# MCU.net
KiCad netlist of a schematic drawn in Altium Designer
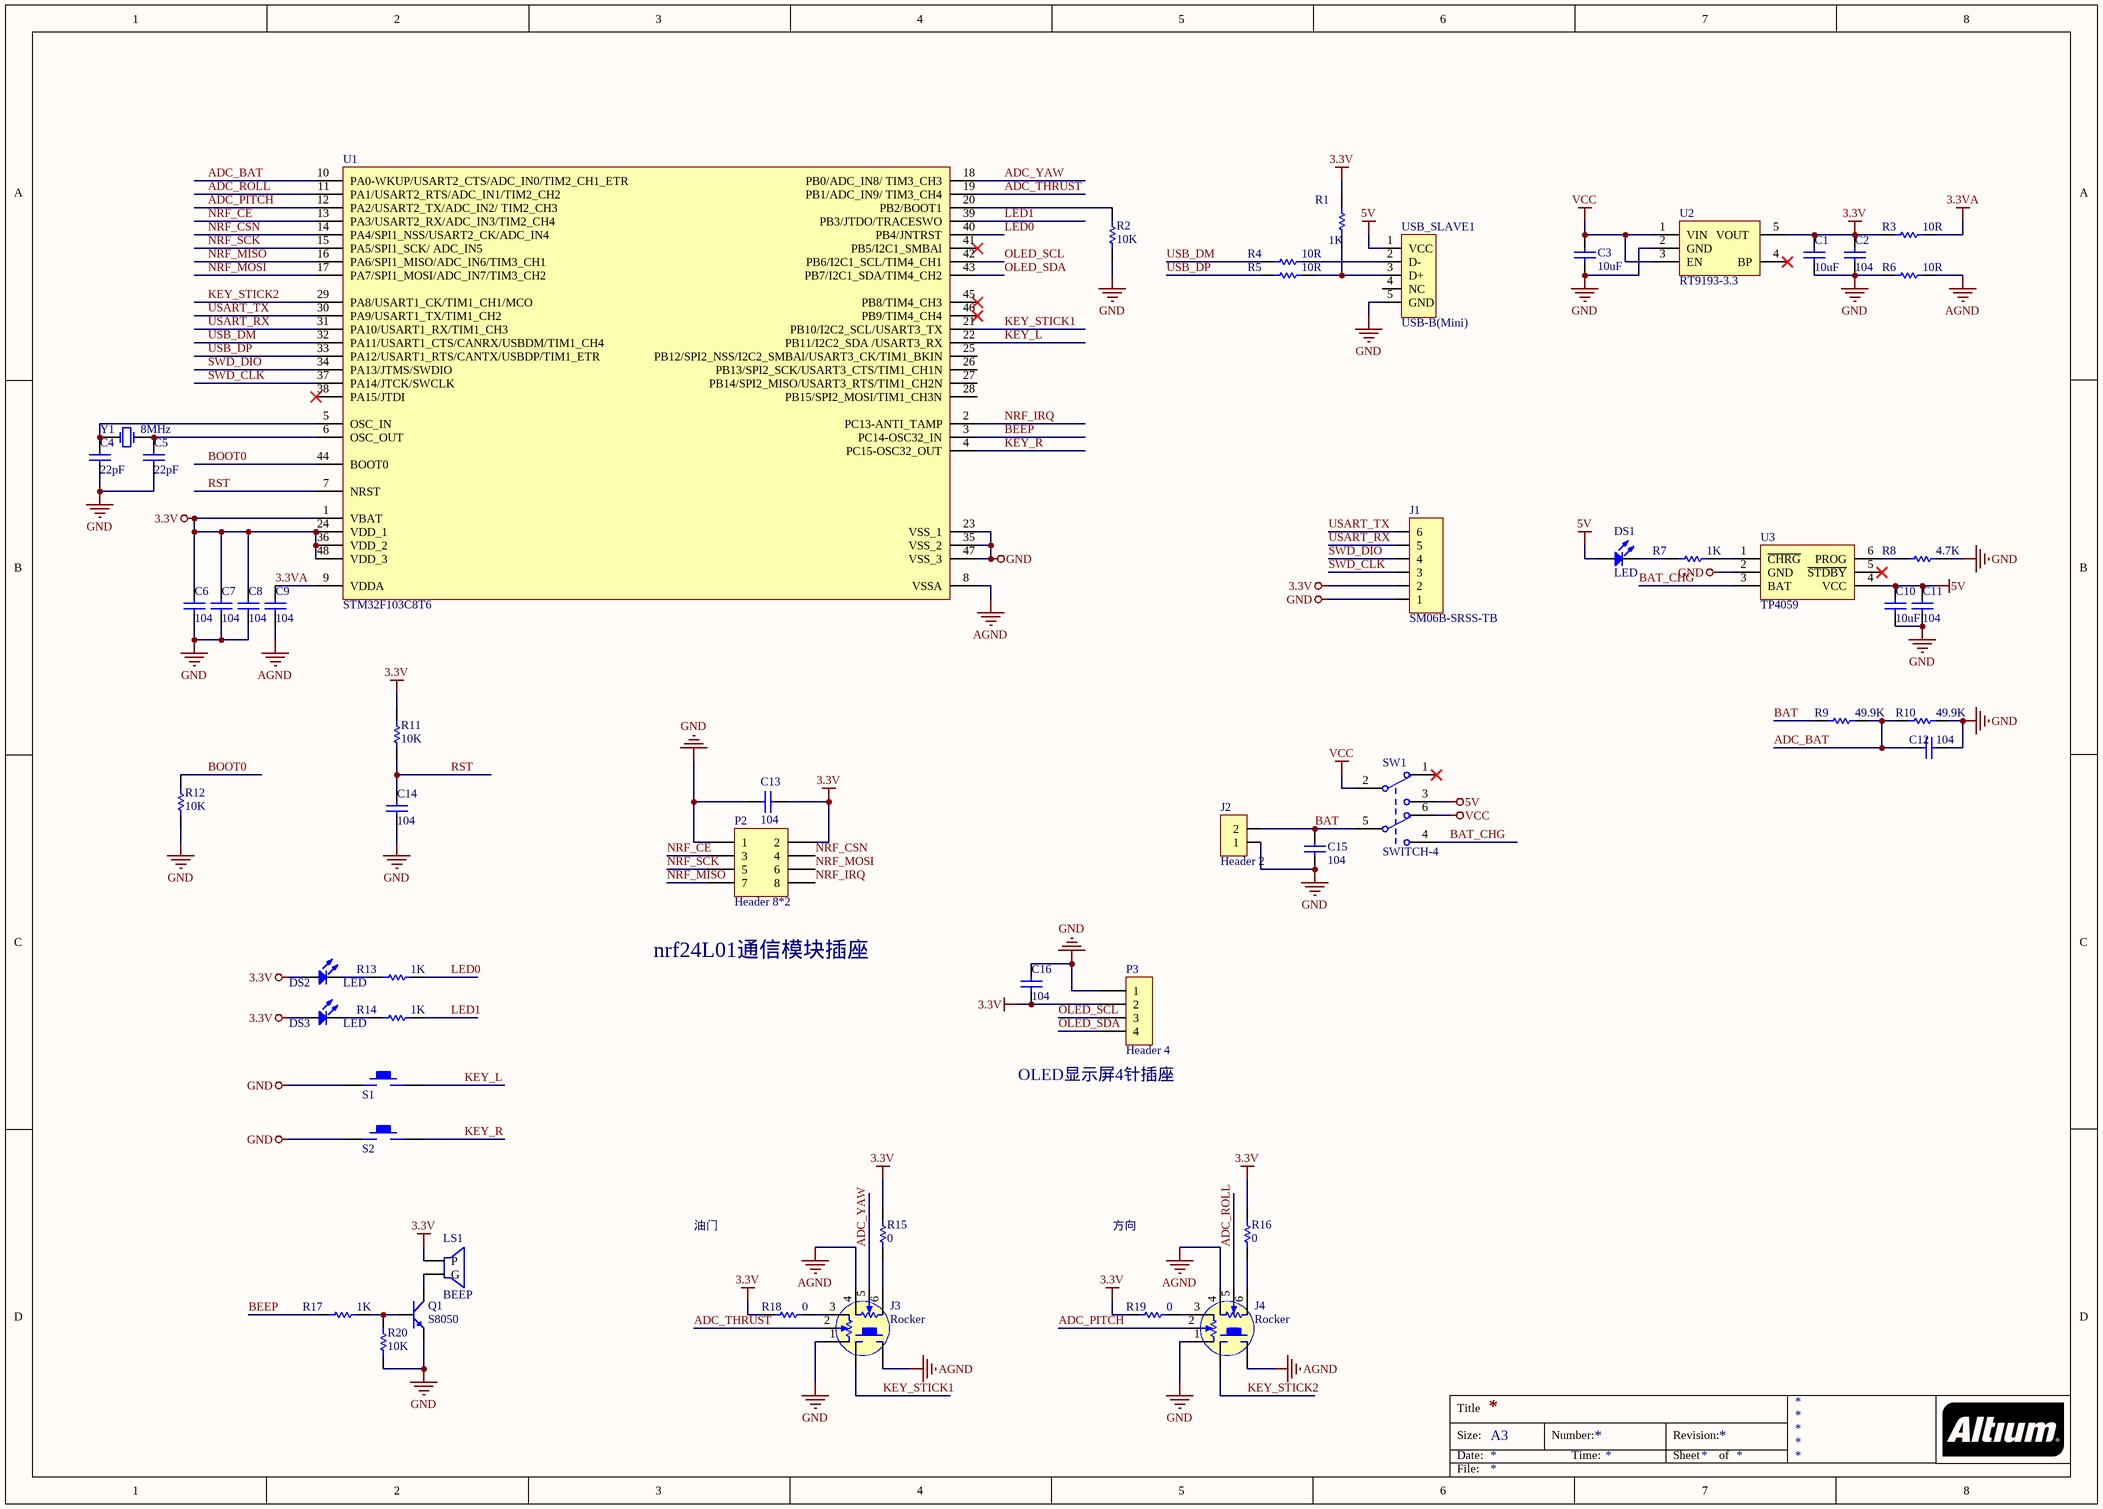
[diagram p0: MCU.SchDoc]

(export (version "E")
  (design (tool "Eeschema 10.0.6"))
  (components
    (comp (ref "C1")
      (value "10uF")
      (footprint "C0603")
      (description "电容")
      (fields (field (name "PUBLISHER") "Altium Limited"))
      (libsource (lib "Devices") (part "C0603"))
    )
    (comp (ref "C2")
      (value "104")
      (footprint "C0603")
      (description "电容")
      (fields (field (name "PUBLISHER") "Altium Limited"))
      (libsource (lib "Devices") (part "C0603"))
    )
    (comp (ref "C3")
      (value "10uF")
      (footprint "C0603")
      (description "电容")
      (fields (field (name "PUBLISHER") "Altium Limited"))
      (libsource (lib "Devices") (part "C0603"))
    )
    (comp (ref "C4")
      (value "22pF")
      (footprint "C0603")
      (description "电容")
      (fields (field (name "PUBLISHER") "Altium Limited"))
      (libsource (lib "Devices") (part "C0603"))
    )
    (comp (ref "C5")
      (value "22pF")
      (footprint "C0603")
      (description "电容")
      (fields (field (name "PUBLISHER") "Altium Limited"))
      (libsource (lib "Devices") (part "C0603"))
    )
    (comp (ref "C6")
      (value "104")
      (footprint "C0603")
      (description "电容")
      (fields (field (name "PUBLISHER") "Altium Limited"))
      (libsource (lib "Devices") (part "C0603"))
    )
    (comp (ref "C7")
      (value "104")
      (footprint "C0603")
      (description "电容")
      (fields (field (name "PUBLISHER") "Altium Limited"))
      (libsource (lib "Devices") (part "C0603"))
    )
    (comp (ref "C8")
      (value "104")
      (footprint "C0603")
      (description "电容")
      (fields (field (name "PUBLISHER") "Altium Limited"))
      (libsource (lib "Devices") (part "C0603"))
    )
    (comp (ref "C9")
      (value "104")
      (footprint "C0603")
      (description "电容")
      (fields (field (name "PUBLISHER") "Altium Limited"))
      (libsource (lib "Devices") (part "C0603"))
    )
    (comp (ref "C10")
      (value "10uF")
      (footprint "C0603")
      (description "电容")
      (fields (field (name "PUBLISHER") "Altium Limited"))
      (libsource (lib "Devices") (part "C0603"))
    )
    (comp (ref "C11")
      (value "104")
      (footprint "C0603")
      (description "电容")
      (fields (field (name "PUBLISHER") "Altium Limited"))
      (libsource (lib "Devices") (part "C0603"))
    )
    (comp (ref "C12")
      (value "104")
      (footprint "C0603")
      (description "电容")
      (fields (field (name "PUBLISHER") "Altium Limited"))
      (libsource (lib "Devices") (part "C0603"))
    )
    (comp (ref "C13")
      (value "104")
      (footprint "C0603")
      (description "电容")
      (fields (field (name "PUBLISHER") "Altium Limited"))
      (libsource (lib "Devices") (part "C0603"))
    )
    (comp (ref "C14")
      (value "104")
      (footprint "C0603")
      (description "电容")
      (fields (field (name "PUBLISHER") "Altium Limited"))
      (libsource (lib "Devices") (part "C0603"))
    )
    (comp (ref "C15")
      (value "104")
      (footprint "C0603")
      (description "电容")
      (fields (field (name "PUBLISHER") "Altium Limited"))
      (libsource (lib "Devices") (part "C0603"))
    )
    (comp (ref "C16")
      (value "104")
      (footprint "C0603")
      (description "电容")
      (fields (field (name "PUBLISHER") "Altium Limited"))
      (libsource (lib "Devices") (part "C0603"))
    )
    (comp (ref "DS1")
      (value "LED")
      (footprint "LED0603")
      (description "Typical RED, GREEN, YELLOW, AMBER GaAs LED")
      (fields (field (name "PUBLISHER") "Altium Limited"))
      (libsource (lib "Devices") (part "LED"))
    )
    (comp (ref "DS2")
      (value "LED")
      (footprint "LED0603")
      (description "Typical RED, GREEN, YELLOW, AMBER GaAs LED")
      (fields (field (name "PUBLISHER") "Altium Limited"))
      (libsource (lib "Devices") (part "LED"))
    )
    (comp (ref "DS3")
      (value "LED")
      (footprint "LED0603")
      (description "Typical RED, GREEN, YELLOW, AMBER GaAs LED")
      (fields (field (name "PUBLISHER") "Altium Limited"))
      (libsource (lib "Devices") (part "LED"))
    )
    (comp (ref "J1")
      (value "SM06B-SRSS-TB")
      (footprint "HDR1X6")
      (libsource (lib "Connectors") (part "SM06B-SRSS-TB"))
    )
    (comp (ref "J2")
      (value "Header 2")
      (footprint "HDR1X2-2MM")
      (description "Header, 2-Pin")
      (fields (field (name "PUBLISHER") "Altium Limited"))
      (libsource (lib "Connectors") (part "Header 2"))
    )
    (comp (ref "J3")
      (value "Rocker")
      (footprint "Rocker-RKJXV1224005")
      (description "航模摇杆")
      (libsource (lib "Devices") (part "Rocker"))
    )
    (comp (ref "J4")
      (value "Rocker")
      (footprint "Rocker-RKJXV1224005")
      (description "航模摇杆")
      (libsource (lib "Devices") (part "Rocker"))
    )
    (comp (ref "LS1")
      (value "BEEP")
      (footprint "BEEP-9")
      (description "蜂鸣器")
      (libsource (lib "Devices") (part "BEEP"))
    )
    (comp (ref "P2")
      (value "Header 8*2")
      (footprint "HDR4*2")
      (description "Header, 8-Pin")
      (fields (field (name "PUBLISHER") "Altium Limited"))
      (libsource (lib "Remoter") (part "Header 4*2"))
    )
    (comp (ref "P3")
      (value "Header 4")
      (footprint "HDR1X4")
      (description "Header, 8-Pin")
      (fields (field (name "PUBLISHER") "Altium Limited"))
      (libsource (lib "Remoter") (part "Header 4"))
    )
    (comp (ref "Q1")
      (value "S8050")
      (footprint "SOT-23R")
      (description "8050/BCW846/BCW847")
      (libsource (lib "Devices") (part "NPN"))
    )
    (comp (ref "R1")
      (value "1K")
      (footprint "R0603")
      (description "电阻")
      (fields (field (name "PUBLISHER") "Altium Limited"))
      (libsource (lib "Devices") (part "RES0603"))
    )
    (comp (ref "R2")
      (value "10K")
      (footprint "R0603")
      (description "电阻")
      (fields (field (name "PUBLISHER") "Altium Limited"))
      (libsource (lib "Devices") (part "RES0603"))
    )
    (comp (ref "R3")
      (value "10R")
      (footprint "R0603")
      (description "电阻")
      (fields (field (name "PUBLISHER") "Altium Limited"))
      (libsource (lib "Devices") (part "RES0603"))
    )
    (comp (ref "R4")
      (value "10R")
      (footprint "R0603")
      (description "电阻")
      (fields (field (name "PUBLISHER") "Altium Limited"))
      (libsource (lib "Devices") (part "RES0603"))
    )
    (comp (ref "R5")
      (value "10R")
      (footprint "R0603")
      (description "电阻")
      (fields (field (name "PUBLISHER") "Altium Limited"))
      (libsource (lib "Devices") (part "RES0603"))
    )
    (comp (ref "R6")
      (value "10R")
      (footprint "R0603")
      (description "电阻")
      (fields (field (name "PUBLISHER") "Altium Limited"))
      (libsource (lib "Devices") (part "RES0603"))
    )
    (comp (ref "R7")
      (value "1K")
      (footprint "R0603")
      (description "电阻")
      (fields (field (name "PUBLISHER") "Altium Limited"))
      (libsource (lib "Devices") (part "RES0603"))
    )
    (comp (ref "R8")
      (value "4.7K")
      (footprint "R0603")
      (description "电阻")
      (fields (field (name "PUBLISHER") "Altium Limited"))
      (libsource (lib "Devices") (part "RES0603"))
    )
    (comp (ref "R9")
      (value "49.9K")
      (footprint "R0603")
      (description "电阻")
      (fields (field (name "PUBLISHER") "Altium Limited"))
      (libsource (lib "Devices") (part "RES0603"))
    )
    (comp (ref "R10")
      (value "49.9K")
      (footprint "R0603")
      (description "电阻")
      (fields (field (name "PUBLISHER") "Altium Limited"))
      (libsource (lib "Devices") (part "RES0603"))
    )
    (comp (ref "R11")
      (value "10K")
      (footprint "R0603")
      (description "电阻")
      (fields (field (name "PUBLISHER") "Altium Limited"))
      (libsource (lib "Devices") (part "RES0603"))
    )
    (comp (ref "R12")
      (value "10K")
      (footprint "R0603")
      (description "电阻")
      (fields (field (name "PUBLISHER") "Altium Limited"))
      (libsource (lib "Devices") (part "RES0603"))
    )
    (comp (ref "R13")
      (value "1K")
      (footprint "R0603")
      (description "电阻")
      (fields (field (name "PUBLISHER") "Altium Limited"))
      (libsource (lib "Devices") (part "RES0603"))
    )
    (comp (ref "R14")
      (value "1K")
      (footprint "R0603")
      (description "电阻")
      (fields (field (name "PUBLISHER") "Altium Limited"))
      (libsource (lib "Devices") (part "RES0603"))
    )
    (comp (ref "R15")
      (value "0")
      (footprint "R0603")
      (description "电阻")
      (fields (field (name "PUBLISHER") "Altium Limited"))
      (libsource (lib "Devices") (part "RES0603"))
    )
    (comp (ref "R16")
      (value "0")
      (footprint "R0603")
      (description "电阻")
      (fields (field (name "PUBLISHER") "Altium Limited"))
      (libsource (lib "Devices") (part "RES0603"))
    )
    (comp (ref "R17")
      (value "1K")
      (footprint "R0603")
      (description "电阻")
      (fields (field (name "PUBLISHER") "Altium Limited"))
      (libsource (lib "Devices") (part "RES0603"))
    )
    (comp (ref "R18")
      (value "0")
      (footprint "R0603")
      (description "电阻")
      (fields (field (name "PUBLISHER") "Altium Limited"))
      (libsource (lib "Devices") (part "RES0603"))
    )
    (comp (ref "R19")
      (value "0")
      (footprint "R0603")
      (description "电阻")
      (fields (field (name "PUBLISHER") "Altium Limited"))
      (libsource (lib "Devices") (part "RES0603"))
    )
    (comp (ref "R20")
      (value "10K")
      (footprint "R0603")
      (description "电阻")
      (fields (field (name "PUBLISHER") "Altium Limited"))
      (libsource (lib "Devices") (part "RES0603"))
    )
    (comp (ref "S1")
      (value "KEY")
      (footprint "KEY-3X6X3.5-C")
      (description "普通轻触按钮")
      (libsource (lib "Devices") (part "KEY"))
    )
    (comp (ref "S2")
      (value "KEY")
      (footprint "KEY-3X6X3.5-C")
      (description "普通轻触按钮")
      (libsource (lib "Devices") (part "KEY"))
    )
    (comp (ref "SW1")
      (value "SWITCH-4")
      (footprint "SW-MSS22D18G2")
      (libsource (lib "Devices") (part "SWITCH-4"))
    )
    (comp (ref "U1")
      (value "STM32F103C8T6")
      (footprint "LQFP-48")
      (libsource (lib "IC") (part "STM32F103C8T6"))
    )
    (comp (ref "U2") (value "RT9193-3.3") (footprint "SOT-23-5") (libsource (lib "IC") (part "RT9193-3.3")))
    (comp (ref "U3")
      (value "TP4059")
      (footprint "SOT23-6")
      (description "锂电池充电IC")
      (libsource (lib "IC") (part "TP4059"))
    )
    (comp (ref "USB_SLAVE1")
      (value "USB-B(Mini)")
      (footprint "USB-MicroUSB")
      (libsource (lib "Connectors") (part "USB5"))
    )
    (comp (ref "Y1")
      (value "8MHz")
      (footprint "X-NX5032GA")
      (description "Crystal Oscillator")
      (fields (field (name "PUBLISHER") "Altium Limited"))
      (libsource (lib "Devices") (part "XTAL"))
    )
  )
  (nets
    (net (code "1") (name "/ADC_BAT") (class "Default")
      (node (ref "C12") (pin "2") (pinfunction "2_2") (pintype "passive"))
      (node (ref "R10") (pin "1") (pinfunction "1_1") (pintype "passive"))
      (node (ref "R9") (pin "2") (pinfunction "2_2") (pintype "passive"))
      (node (ref "U1") (pin "10") (pinfunction "PA0-WKUP/USART2_CTS/ADC_IN0/TIM2_CH1_ETR_10") (pintype "passive"))
    )
    (net (code "2") (name "/ADC_PITCH") (class "Default")
      (node (ref "J4") (pin "2") (pinfunction "2_2") (pintype "passive"))
      (node (ref "U1") (pin "12") (pinfunction "PA2/USART2_TX/ADC_IN2/_TIM2_CH3_12") (pintype "passive"))
    )
    (net (code "3") (name "/ADC_ROLL") (class "Default")
      (node (ref "J4") (pin "5") (pinfunction "5_5") (pintype "passive"))
      (node (ref "U1") (pin "11") (pinfunction "PA1/USART2_RTS/ADC_IN1/TIM2_CH2_11") (pintype "passive"))
    )
    (net (code "4") (name "/ADC_THRUST") (class "Default")
      (node (ref "J3") (pin "2") (pinfunction "2_2") (pintype "passive"))
      (node (ref "U1") (pin "19") (pinfunction "PB1/ADC_IN9/_TIM3_CH4_19") (pintype "passive"))
    )
    (net (code "5") (name "/ADC_YAW") (class "Default")
      (node (ref "J3") (pin "5") (pinfunction "5_5") (pintype "passive"))
      (node (ref "U1") (pin "18") (pinfunction "PB0/ADC_IN8/_TIM3_CH3_18") (pintype "passive"))
    )
    (net (code "6") (name "/BAT") (class "Default")
      (node (ref "C15") (pin "1") (pinfunction "1_1") (pintype "passive"))
      (node (ref "J2") (pin "2") (pinfunction "2_2") (pintype "passive"))
      (node (ref "R9") (pin "1") (pinfunction "1_1") (pintype "passive"))
      (node (ref "SW1") (pin "5") (pinfunction "5_5") (pintype "passive"))
    )
    (net (code "7") (name "/BAT_CHG") (class "Default")
      (node (ref "SW1") (pin "4") (pinfunction "4_4") (pintype "passive"))
      (node (ref "U3") (pin "3") (pinfunction "BAT_3") (pintype "passive"))
    )
    (net (code "8") (name "/BEEP") (class "Default")
      (node (ref "R17") (pin "1") (pinfunction "1_1") (pintype "passive"))
      (node (ref "U1") (pin "3") (pinfunction "PC14-OSC32_IN_3") (pintype "passive"))
    )
    (net (code "9") (name "/BOOT0") (class "Default")
      (node (ref "R12") (pin "2") (pinfunction "2_2") (pintype "passive"))
      (node (ref "U1") (pin "44") (pinfunction "BOOT0_44") (pintype "passive"))
    )
    (net (code "10") (name "/KEY_L") (class "Default")
      (node (ref "S1") (pin "2") (pinfunction "2_2") (pintype "passive"))
      (node (ref "U1") (pin "22") (pinfunction "PB11/I2C2_SDA_/USART3_RX_22") (pintype "passive"))
    )
    (net (code "11") (name "/KEY_R") (class "Default")
      (node (ref "S2") (pin "2") (pinfunction "2_2") (pintype "passive"))
      (node (ref "U1") (pin "4") (pinfunction "PC15-OSC32_OUT_4") (pintype "passive"))
    )
    (net (code "12") (name "/KEY_STICK1") (class "Default")
      (node (ref "J3") (pin "J2") (pinfunction "J2_J2") (pintype "passive"))
      (node (ref "U1") (pin "21") (pinfunction "PB10/I2C2_SCL/USART3_TX_21") (pintype "passive"))
    )
    (net (code "13") (name "/KEY_STICK2") (class "Default")
      (node (ref "J4") (pin "J2") (pinfunction "J2_J2") (pintype "passive"))
      (node (ref "U1") (pin "29") (pinfunction "PA8/USART1_CK/TIM1_CH1/MCO_29") (pintype "passive"))
    )
    (net (code "14") (name "/LED0") (class "Default")
      (node (ref "R13") (pin "2") (pinfunction "2_2") (pintype "passive"))
      (node (ref "U1") (pin "40") (pinfunction "PB4/JNTRST_40") (pintype "passive"))
    )
    (net (code "15") (name "/LED1") (class "Default")
      (node (ref "R14") (pin "2") (pinfunction "2_2") (pintype "passive"))
      (node (ref "U1") (pin "39") (pinfunction "PB3/JTDO/TRACESWO_39") (pintype "passive"))
    )
    (net (code "16") (name "/NRF_CE") (class "Default")
      (node (ref "P2") (pin "3") (pinfunction "3_3") (pintype "passive"))
      (node (ref "U1") (pin "13") (pinfunction "PA3/USART2_RX/ADC_IN3/TIM2_CH4_13") (pintype "passive"))
    )
    (net (code "17") (name "/NRF_CSN") (class "Default")
      (node (ref "P2") (pin "4") (pinfunction "4_4") (pintype "passive"))
      (node (ref "U1") (pin "14") (pinfunction "PA4/SPI1_NSS/USART2_CK/ADC_IN4_14") (pintype "passive"))
    )
    (net (code "18") (name "/NRF_IRQ") (class "Default")
      (node (ref "P2") (pin "8") (pinfunction "8_8") (pintype "passive"))
      (node (ref "U1") (pin "2") (pinfunction "PC13-ANTI_TAMP_2") (pintype "passive"))
    )
    (net (code "19") (name "/NRF_MISO") (class "Default")
      (node (ref "P2") (pin "7") (pinfunction "7_7") (pintype "passive"))
      (node (ref "U1") (pin "16") (pinfunction "PA6/SPI1_MISO/ADC_IN6/TIM3_CH1_16") (pintype "passive"))
    )
    (net (code "20") (name "/NRF_MOSI") (class "Default")
      (node (ref "P2") (pin "6") (pinfunction "6_6") (pintype "passive"))
      (node (ref "U1") (pin "17") (pinfunction "PA7/SPI1_MOSI/ADC_IN7/TIM3_CH2_17") (pintype "passive"))
    )
    (net (code "21") (name "/NRF_SCK") (class "Default")
      (node (ref "P2") (pin "5") (pinfunction "5_5") (pintype "passive"))
      (node (ref "U1") (pin "15") (pinfunction "PA5/SPI1_SCK/_ADC_IN5_15") (pintype "passive"))
    )
    (net (code "22") (name "/OLED_SCL") (class "Default")
      (node (ref "P3") (pin "3") (pinfunction "3_3") (pintype "passive"))
      (node (ref "U1") (pin "42") (pinfunction "PB6/I2C1_SCL/TIM4_CH1_42") (pintype "passive"))
    )
    (net (code "23") (name "/OLED_SDA") (class "Default")
      (node (ref "P3") (pin "4") (pinfunction "4_4") (pintype "passive"))
      (node (ref "U1") (pin "43") (pinfunction "PB7/I2C1_SDA/TIM4_CH2_43") (pintype "passive"))
    )
    (net (code "24") (name "/RST") (class "Default")
      (node (ref "C14") (pin "2") (pinfunction "2_2") (pintype "passive"))
      (node (ref "R11") (pin "1") (pinfunction "1_1") (pintype "passive"))
      (node (ref "U1") (pin "7") (pinfunction "NRST_7") (pintype "passive"))
    )
    (net (code "25") (name "/SWD_CLK") (class "Default")
      (node (ref "J1") (pin "3") (pinfunction "3_3") (pintype "passive"))
      (node (ref "U1") (pin "37") (pinfunction "PA14/JTCK/SWCLK_37") (pintype "passive"))
    )
    (net (code "26") (name "/SWD_DIO") (class "Default")
      (node (ref "J1") (pin "4") (pinfunction "4_4") (pintype "passive"))
      (node (ref "U1") (pin "34") (pinfunction "PA13/JTMS/SWDIO_34") (pintype "passive"))
    )
    (net (code "27") (name "/USART_RX") (class "Default")
      (node (ref "J1") (pin "5") (pinfunction "5_5") (pintype "passive"))
      (node (ref "U1") (pin "31") (pinfunction "PA10/USART1_RX/TIM1_CH3_31") (pintype "passive"))
    )
    (net (code "28") (name "/USART_TX") (class "Default")
      (node (ref "J1") (pin "6") (pinfunction "6_6") (pintype "passive"))
      (node (ref "U1") (pin "30") (pinfunction "PA9/USART1_TX/TIM1_CH2_30") (pintype "passive"))
    )
    (net (code "29") (name "/USB_DM") (class "Default")
      (node (ref "R4") (pin "1") (pinfunction "1_1") (pintype "passive"))
      (node (ref "U1") (pin "32") (pinfunction "PA11/USART1_CTS/CANRX/USBDM/TIM1_CH4_32") (pintype "passive"))
    )
    (net (code "30") (name "/USB_DP") (class "Default")
      (node (ref "R5") (pin "1") (pinfunction "1_1") (pintype "passive"))
      (node (ref "U1") (pin "33") (pinfunction "PA12/USART1_RTS/CANTX/USBDP/TIM1_ETR_33") (pintype "passive"))
    )
    (net (code "31") (name "3.3V") (class "Default")
      (node (ref "C1") (pin "2") (pinfunction "2_2") (pintype "passive"))
      (node (ref "C13") (pin "2") (pinfunction "2_2") (pintype "passive"))
      (node (ref "C16") (pin "2") (pinfunction "2_2") (pintype "passive"))
      (node (ref "C2") (pin "2") (pinfunction "2_2") (pintype "passive"))
      (node (ref "C6") (pin "2") (pinfunction "2_2") (pintype "passive"))
      (node (ref "C7") (pin "2") (pinfunction "2_2") (pintype "passive"))
      (node (ref "C8") (pin "2") (pinfunction "2_2") (pintype "passive"))
      (node (ref "DS2") (pin "1") (pinfunction "A_1") (pintype "passive"))
      (node (ref "DS3") (pin "1") (pinfunction "A_1") (pintype "passive"))
      (node (ref "J1") (pin "2") (pinfunction "2_2") (pintype "passive"))
      (node (ref "LS1") (pin "1") (pinfunction "P_1") (pintype "passive"))
      (node (ref "P2") (pin "2") (pinfunction "2_2") (pintype "passive"))
      (node (ref "P3") (pin "2") (pinfunction "2_2") (pintype "passive"))
      (node (ref "R1") (pin "2") (pinfunction "2_2") (pintype "passive"))
      (node (ref "R11") (pin "2") (pinfunction "2_2") (pintype "passive"))
      (node (ref "R15") (pin "2") (pinfunction "2_2") (pintype "passive"))
      (node (ref "R16") (pin "2") (pinfunction "2_2") (pintype "passive"))
      (node (ref "R18") (pin "2") (pinfunction "2_2") (pintype "passive"))
      (node (ref "R19") (pin "2") (pinfunction "2_2") (pintype "passive"))
      (node (ref "R3") (pin "1") (pinfunction "1_1") (pintype "passive"))
      (node (ref "U1") (pin "1") (pinfunction "VBAT_1") (pintype "passive"))
      (node (ref "U1") (pin "24") (pinfunction "VDD_1_24") (pintype "passive"))
      (node (ref "U1") (pin "36") (pinfunction "VDD_2_36") (pintype "passive"))
      (node (ref "U1") (pin "48") (pinfunction "VDD_3_48") (pintype "passive"))
      (node (ref "U2") (pin "5") (pinfunction "VOUT_5") (pintype "passive"))
    )
    (net (code "32") (name "3.3VA") (class "Default")
      (node (ref "C9") (pin "2") (pinfunction "2_2") (pintype "passive"))
      (node (ref "R3") (pin "2") (pinfunction "2_2") (pintype "passive"))
      (node (ref "U1") (pin "9") (pinfunction "VDDA_9") (pintype "passive"))
    )
    (net (code "33") (name "5V") (class "Default")
      (node (ref "C10") (pin "2") (pinfunction "2_2") (pintype "passive"))
      (node (ref "C11") (pin "2") (pinfunction "2_2") (pintype "passive"))
      (node (ref "DS1") (pin "1") (pinfunction "A_1") (pintype "passive"))
      (node (ref "SW1") (pin "3") (pinfunction "3_3") (pintype "passive"))
      (node (ref "U3") (pin "4") (pinfunction "VCC_4") (pintype "passive"))
      (node (ref "USB_SLAVE1") (pin "1") (pinfunction "VCC_1") (pintype "passive"))
    )
    (net (code "34") (name "AGND") (class "Default")
      (node (ref "C9") (pin "1") (pinfunction "1_1") (pintype "passive"))
      (node (ref "J3") (pin "4") (pinfunction "4_4") (pintype "passive"))
      (node (ref "J3") (pin "J1") (pinfunction "J1_J1") (pintype "passive"))
      (node (ref "J4") (pin "4") (pinfunction "4_4") (pintype "passive"))
      (node (ref "J4") (pin "J1") (pinfunction "J1_J1") (pintype "passive"))
      (node (ref "R6") (pin "2") (pinfunction "2_2") (pintype "passive"))
      (node (ref "U1") (pin "8") (pinfunction "VSSA_8") (pintype "passive"))
    )
    (net (code "35") (name "GND") (class "Default")
      (node (ref "C1") (pin "1") (pinfunction "1_1") (pintype "passive"))
      (node (ref "C10") (pin "1") (pinfunction "1_1") (pintype "passive"))
      (node (ref "C11") (pin "1") (pinfunction "1_1") (pintype "passive"))
      (node (ref "C12") (pin "1") (pinfunction "1_1") (pintype "passive"))
      (node (ref "C13") (pin "1") (pinfunction "1_1") (pintype "passive"))
      (node (ref "C14") (pin "1") (pinfunction "1_1") (pintype "passive"))
      (node (ref "C15") (pin "2") (pinfunction "2_2") (pintype "passive"))
      (node (ref "C16") (pin "1") (pinfunction "1_1") (pintype "passive"))
      (node (ref "C2") (pin "1") (pinfunction "1_1") (pintype "passive"))
      (node (ref "C3") (pin "1") (pinfunction "1_1") (pintype "passive"))
      (node (ref "C4") (pin "1") (pinfunction "1_1") (pintype "passive"))
      (node (ref "C5") (pin "1") (pinfunction "1_1") (pintype "passive"))
      (node (ref "C6") (pin "1") (pinfunction "1_1") (pintype "passive"))
      (node (ref "C7") (pin "1") (pinfunction "1_1") (pintype "passive"))
      (node (ref "C8") (pin "1") (pinfunction "1_1") (pintype "passive"))
      (node (ref "J1") (pin "1") (pinfunction "1_1") (pintype "passive"))
      (node (ref "J2") (pin "1") (pinfunction "1_1") (pintype "passive"))
      (node (ref "J3") (pin "1") (pinfunction "1_1") (pintype "passive"))
      (node (ref "J4") (pin "1") (pinfunction "1_1") (pintype "passive"))
      (node (ref "P2") (pin "1") (pinfunction "1_1") (pintype "passive"))
      (node (ref "P3") (pin "1") (pinfunction "1_1") (pintype "passive"))
      (node (ref "Q1") (pin "1") (pinfunction "E_1") (pintype "passive"))
      (node (ref "R10") (pin "2") (pinfunction "2_2") (pintype "passive"))
      (node (ref "R12") (pin "1") (pinfunction "1_1") (pintype "passive"))
      (node (ref "R2") (pin "1") (pinfunction "1_1") (pintype "passive"))
      (node (ref "R20") (pin "1") (pinfunction "1_1") (pintype "passive"))
      (node (ref "R6") (pin "1") (pinfunction "1_1") (pintype "passive"))
      (node (ref "R8") (pin "2") (pinfunction "2_2") (pintype "passive"))
      (node (ref "S1") (pin "1") (pinfunction "1_1") (pintype "passive"))
      (node (ref "S2") (pin "1") (pinfunction "1_1") (pintype "passive"))
      (node (ref "U1") (pin "23") (pinfunction "VSS_1_23") (pintype "passive"))
      (node (ref "U1") (pin "35") (pinfunction "VSS_2_35") (pintype "passive"))
      (node (ref "U1") (pin "47") (pinfunction "VSS_3_47") (pintype "passive"))
      (node (ref "U2") (pin "2") (pinfunction "GND_2") (pintype "passive"))
      (node (ref "U3") (pin "2") (pinfunction "GND_2") (pintype "passive"))
      (node (ref "USB_SLAVE1") (pin "5") (pinfunction "GND_5") (pintype "passive"))
    )
    (net (code "36") (name "Net-(DS1-K)") (class "Default")
      (node (ref "DS1") (pin "2") (pinfunction "K_2") (pintype "passive"))
      (node (ref "R7") (pin "1") (pinfunction "1_1") (pintype "passive"))
    )
    (net (code "37") (name "Net-(DS2-K)") (class "Default")
      (node (ref "DS2") (pin "2") (pinfunction "K_2") (pintype "passive"))
      (node (ref "R13") (pin "1") (pinfunction "1_1") (pintype "passive"))
    )
    (net (code "38") (name "Net-(DS3-K)") (class "Default")
      (node (ref "DS3") (pin "2") (pinfunction "K_2") (pintype "passive"))
      (node (ref "R14") (pin "1") (pinfunction "1_1") (pintype "passive"))
    )
    (net (code "39") (name "Net-(J3-Pad3)") (class "Default")
      (node (ref "J3") (pin "3") (pinfunction "3_3") (pintype "passive"))
      (node (ref "R18") (pin "1") (pinfunction "1_1") (pintype "passive"))
    )
    (net (code "40") (name "Net-(J3-Pad6)") (class "Default")
      (node (ref "J3") (pin "6") (pinfunction "6_6") (pintype "passive"))
      (node (ref "R15") (pin "1") (pinfunction "1_1") (pintype "passive"))
    )
    (net (code "41") (name "Net-(J4-Pad3)") (class "Default")
      (node (ref "J4") (pin "3") (pinfunction "3_3") (pintype "passive"))
      (node (ref "R19") (pin "1") (pinfunction "1_1") (pintype "passive"))
    )
    (net (code "42") (name "Net-(J4-Pad6)") (class "Default")
      (node (ref "J4") (pin "6") (pinfunction "6_6") (pintype "passive"))
      (node (ref "R16") (pin "1") (pinfunction "1_1") (pintype "passive"))
    )
    (net (code "43") (name "Net-(LS1-G)") (class "Default")
      (node (ref "LS1") (pin "2") (pinfunction "G_2") (pintype "passive"))
      (node (ref "Q1") (pin "3") (pinfunction "C_3") (pintype "passive"))
    )
    (net (code "44") (name "Net-(Q1-B)") (class "Default")
      (node (ref "Q1") (pin "2") (pinfunction "B_2") (pintype "passive"))
      (node (ref "R17") (pin "2") (pinfunction "2_2") (pintype "passive"))
      (node (ref "R20") (pin "2") (pinfunction "2_2") (pintype "passive"))
    )
    (net (code "45") (name "Net-(U1-OSC_IN)") (class "Default")
      (node (ref "C4") (pin "2") (pinfunction "2_2") (pintype "passive"))
      (node (ref "U1") (pin "5") (pinfunction "OSC_IN_5") (pintype "passive"))
      (node (ref "Y1") (pin "1") (pinfunction "OSC1_1") (pintype "passive"))
    )
    (net (code "46") (name "Net-(U1-OSC_OUT)") (class "Default")
      (node (ref "C5") (pin "2") (pinfunction "2_2") (pintype "passive"))
      (node (ref "U1") (pin "6") (pinfunction "OSC_OUT_6") (pintype "passive"))
      (node (ref "Y1") (pin "2") (pinfunction "OSC2_2") (pintype "passive"))
    )
    (net (code "47") (name "Net-(U1-PB2{slash}BOOT1)") (class "Default")
      (node (ref "R2") (pin "2") (pinfunction "2_2") (pintype "passive"))
      (node (ref "U1") (pin "20") (pinfunction "PB2/BOOT1_20") (pintype "passive"))
    )
    (net (code "48") (name "Net-(U3-PROG)") (class "Default")
      (node (ref "R8") (pin "1") (pinfunction "1_1") (pintype "passive"))
      (node (ref "U3") (pin "6") (pinfunction "PROG_6") (pintype "passive"))
    )
    (net (code "49") (name "Net-(U3-~{CHRG})") (class "Default")
      (node (ref "R7") (pin "2") (pinfunction "2_2") (pintype "passive"))
      (node (ref "U3") (pin "1") (pinfunction "~{CHRG}_1") (pintype "passive"))
    )
    (net (code "50") (name "Net-(USB_SLAVE1-D+)") (class "Default")
      (node (ref "R1") (pin "1") (pinfunction "1_1") (pintype "passive"))
      (node (ref "R5") (pin "2") (pinfunction "2_2") (pintype "passive"))
      (node (ref "USB_SLAVE1") (pin "3") (pinfunction "D+_3") (pintype "passive"))
    )
    (net (code "51") (name "Net-(USB_SLAVE1-D-)") (class "Default")
      (node (ref "R4") (pin "2") (pinfunction "2_2") (pintype "passive"))
      (node (ref "USB_SLAVE1") (pin "2") (pinfunction "D-_2") (pintype "passive"))
    )
    (net (code "52") (name "VCC") (class "Default")
      (node (ref "C3") (pin "2") (pinfunction "2_2") (pintype "passive"))
      (node (ref "SW1") (pin "2") (pinfunction "2_2") (pintype "passive"))
      (node (ref "SW1") (pin "6") (pinfunction "6_6") (pintype "passive"))
      (node (ref "U2") (pin "1") (pinfunction "VIN_1") (pintype "passive"))
      (node (ref "U2") (pin "3") (pinfunction "EN_3") (pintype "passive"))
    )
    (net (code "53") (name "unconnected-(SW1-Pad1)") (class "Default")
      (node (ref "SW1") (pin "1") (pinfunction "1_1") (pintype "passive+no_connect"))
    )
    (net (code "54") (name "unconnected-(U1-PA15{slash}JTDI-Pad38)") (class "Default")
      (node (ref "U1") (pin "38") (pinfunction "PA15/JTDI_38") (pintype "passive+no_connect"))
    )
    (net (code "55") (name "unconnected-(U1-PB5{slash}I2C1_SMBAl-Pad41)") (class "Default")
      (node (ref "U1") (pin "41") (pinfunction "PB5/I2C1_SMBAl_41") (pintype "passive+no_connect"))
    )
    (net (code "56") (name "unconnected-(U1-PB8{slash}TIM4_CH3-Pad45)") (class "Default")
      (node (ref "U1") (pin "45") (pinfunction "PB8/TIM4_CH3_45") (pintype "passive+no_connect"))
    )
    (net (code "57") (name "unconnected-(U1-PB9{slash}TIM4_CH4-Pad46)") (class "Default")
      (node (ref "U1") (pin "46") (pinfunction "PB9/TIM4_CH4_46") (pintype "passive+no_connect"))
    )
    (net (code "58") (name "unconnected-(U1-PB12{slash}SPI2_NSS{slash}I2C2_SMBAl{slash}USART3_CK{slash}TIM1_BKIN-Pad25)") (class "Default")
      (node (ref "U1") (pin "25") (pinfunction "PB12/SPI2_NSS/I2C2_SMBAl/USART3_CK/TIM1_BKIN_25") (pintype "passive"))
    )
    (net (code "59") (name "unconnected-(U1-PB13{slash}SPI2_SCK{slash}USART3_CTS{slash}TIM1_CH1N-Pad26)") (class "Default")
      (node (ref "U1") (pin "26") (pinfunction "PB13/SPI2_SCK/USART3_CTS/TIM1_CH1N_26") (pintype "passive"))
    )
    (net (code "60") (name "unconnected-(U1-PB14{slash}SPI2_MISO{slash}USART3_RTS{slash}TIM1_CH2N-Pad27)") (class "Default")
      (node (ref "U1") (pin "27") (pinfunction "PB14/SPI2_MISO/USART3_RTS/TIM1_CH2N_27") (pintype "passive"))
    )
    (net (code "61") (name "unconnected-(U1-PB15{slash}SPI2_MOSI{slash}TIM1_CH3N-Pad28)") (class "Default")
      (node (ref "U1") (pin "28") (pinfunction "PB15/SPI2_MOSI/TIM1_CH3N_28") (pintype "passive"))
    )
    (net (code "62") (name "unconnected-(U2-BP-Pad4)") (class "Default")
      (node (ref "U2") (pin "4") (pinfunction "BP_4") (pintype "passive+no_connect"))
    )
    (net (code "63") (name "unconnected-(U3-~{STDBY}-Pad5)") (class "Default")
      (node (ref "U3") (pin "5") (pinfunction "~{STDBY}_5") (pintype "passive+no_connect"))
    )
    (net (code "64") (name "unconnected-(USB_SLAVE1-NC-Pad4)") (class "Default")
      (node (ref "USB_SLAVE1") (pin "4") (pinfunction "NC_4") (pintype "passive"))
    )
  )
)
